# ft231x-breakout.net
KiCad netlist of a schematic drawn in EAGLE
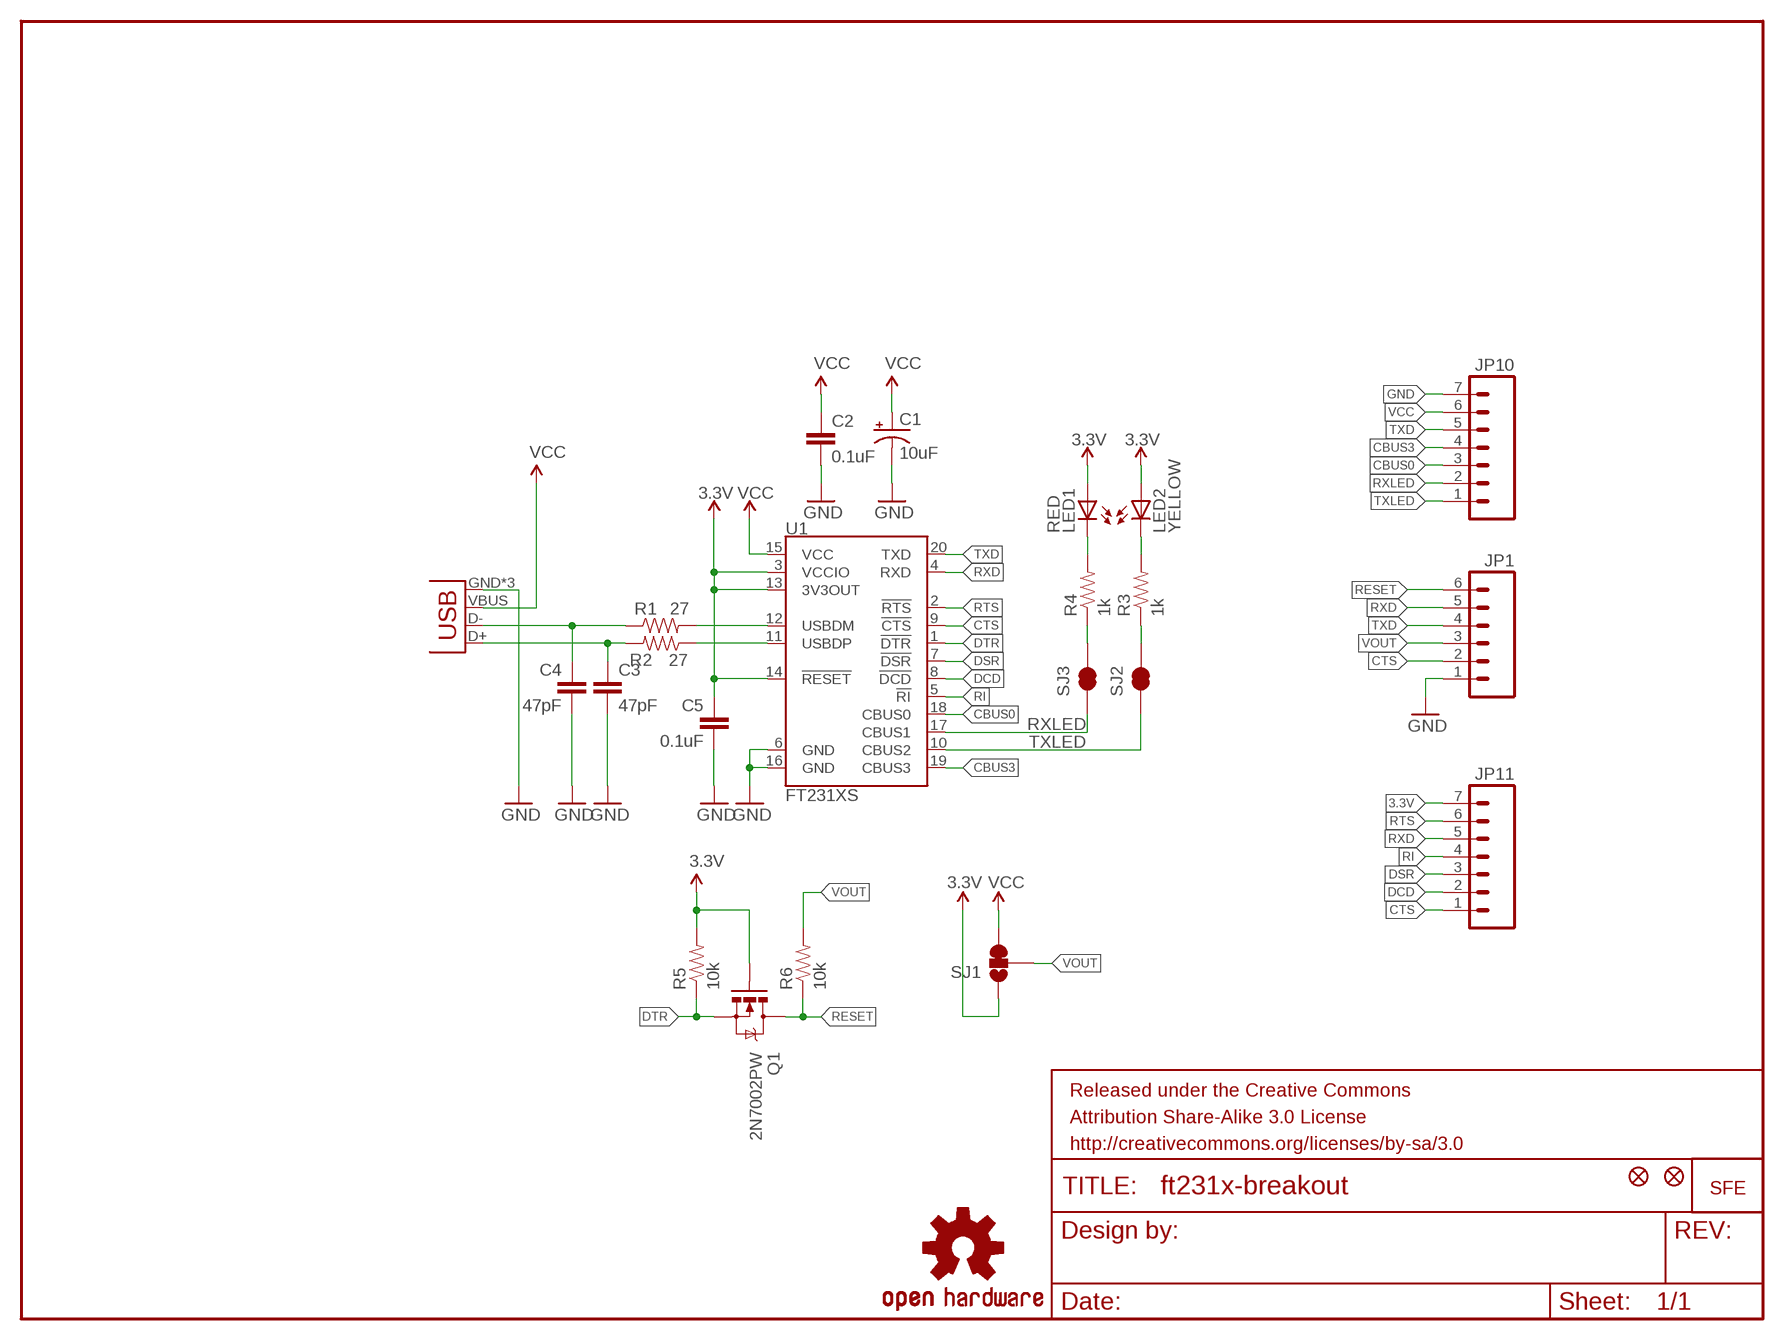
[diagram p0: schematic, sheet 1]

(export (version "E")
  (design (tool "Eeschema 10.0.6"))
  (components
    (comp (ref "C1")
      (value "10uF")
      (footprint "eagle-import:EIA3216")
      (libsource (lib "eagle-import") (part "CAP_POL1206"))
    )
    (comp (ref "C2")
      (value "0.1uF")
      (footprint "eagle-import:0402-CAP")
      (libsource (lib "eagle-import") (part "CAP0402-CAP"))
    )
    (comp (ref "C3")
      (value "47pF")
      (footprint "eagle-import:0402-CAP")
      (libsource (lib "eagle-import") (part "CAP0402-CAP"))
    )
    (comp (ref "C4")
      (value "47pF")
      (footprint "eagle-import:0402-CAP")
      (libsource (lib "eagle-import") (part "CAP0402-CAP"))
    )
    (comp (ref "C5")
      (value "0.1uF")
      (footprint "eagle-import:0402-CAP")
      (libsource (lib "eagle-import") (part "CAP0402-CAP"))
    )
    (comp (ref "FRAME1")
      (value "FRAME-LETTER")
      (footprint "eagle-import:CREATIVE_COMMONS")
      (libsource (lib "eagle-import") (part "FRAME-LETTER"))
    )
    (comp (ref "JP1")
      (value "M06SIP-NS")
      (footprint "eagle-import:1X06_NS")
      (libsource (lib "eagle-import") (part "M06SIP-NS"))
    )
    (comp (ref "JP2")
      (value "LOGO-SFENW2")
      (footprint "eagle-import:SFE-NEW-WEB")
      (libsource (lib "eagle-import") (part "LOGO-SFENW2"))
    )
    (comp (ref "JP3")
      (value "FIDUCIALUFIDUCIAL")
      (footprint "eagle-import:MICRO-FIDUCIAL")
      (libsource (lib "eagle-import") (part "FIDUCIALUFIDUCIAL"))
    )
    (comp (ref "JP4")
      (value "FIDUCIALUFIDUCIAL")
      (footprint "eagle-import:MICRO-FIDUCIAL")
      (libsource (lib "eagle-import") (part "FIDUCIALUFIDUCIAL"))
    )
    (comp (ref "JP10")
      (value "M07NS")
      (footprint "eagle-import:1X07_NS")
      (libsource (lib "eagle-import") (part "M07NS"))
    )
    (comp (ref "JP11")
      (value "M07NS")
      (footprint "eagle-import:1X07_NS")
      (libsource (lib "eagle-import") (part "M07NS"))
    )
    (comp (ref "LED1")
      (value "RED")
      (footprint "eagle-import:LED-0603")
      (libsource (lib "eagle-import") (part "LED0603"))
    )
    (comp (ref "LED2")
      (value "YELLOW")
      (footprint "eagle-import:LED-0603")
      (libsource (lib "eagle-import") (part "LED0603"))
    )
    (comp (ref "Q1")
      (value "2N7002PW")
      (footprint "eagle-import:SOT323")
      (libsource (lib "eagle-import") (part "MOSFET-NCHANNELSOT323"))
    )
    (comp (ref "R1")
      (value "27")
      (footprint "eagle-import:0402-RES")
      (libsource (lib "eagle-import") (part "SparkFun-Resistors_RESISTOR0402-RES"))
    )
    (comp (ref "R2")
      (value "27")
      (footprint "eagle-import:0402-RES")
      (libsource (lib "eagle-import") (part "SparkFun-Resistors_RESISTOR0402-RES"))
    )
    (comp (ref "R3")
      (value "1k")
      (footprint "eagle-import:0402-RES")
      (libsource (lib "eagle-import") (part "RESISTOR0402-RES"))
    )
    (comp (ref "R4")
      (value "1k")
      (footprint "eagle-import:0402-RES")
      (libsource (lib "eagle-import") (part "RESISTOR0402-RES"))
    )
    (comp (ref "R5")
      (value "10k")
      (footprint "eagle-import:0402-RES")
      (libsource (lib "eagle-import") (part "RESISTOR0402-RES"))
    )
    (comp (ref "R6")
      (value "10k")
      (footprint "eagle-import:0402-RES")
      (libsource (lib "eagle-import") (part "RESISTOR0402-RES"))
    )
    (comp (ref "SJ1")
      (value "SOLDERJUMPER_2WAYS")
      (footprint "eagle-import:SJ_3")
      (libsource (lib "eagle-import") (part "SOLDERJUMPER_2WAYS"))
    )
    (comp (ref "SJ2")
      (value "TXLED")
      (footprint "eagle-import:SJ_2S-TRACE")
      (libsource (lib "eagle-import") (part "SOLDERJUMPERTRACE"))
    )
    (comp (ref "SJ3")
      (value "RXLED")
      (footprint "eagle-import:SJ_2S-TRACE")
      (libsource (lib "eagle-import") (part "SOLDERJUMPERTRACE"))
    )
    (comp (ref "U$1")
      (value "OSHW-LOGOS")
      (footprint "eagle-import:OSHW-LOGO-S")
      (libsource (lib "eagle-import") (part "OSHW-LOGOS"))
    )
    (comp (ref "U1")
      (value "FT231XS")
      (footprint "eagle-import:SSOP20_L")
      (libsource (lib "eagle-import") (part "FT231XS"))
    )
    (comp (ref "X1")
      (value "USB-MICROB")
      (footprint "eagle-import:USB-MICROB")
      (libsource (lib "eagle-import") (part "USB-MICROB"))
    )
  )
  (nets
    (net (code "1") (name "3.3V") (class "Default")
      (node (ref "C5") (pin "1") (pinfunction "1_1") (pintype "passive"))
      (node (ref "JP11") (pin "7") (pinfunction "7_7") (pintype "passive"))
      (node (ref "LED1") (pin "A") (pinfunction "A_A") (pintype "passive"))
      (node (ref "LED2") (pin "A") (pinfunction "A_A") (pintype "passive"))
      (node (ref "Q1") (pin "1") (pinfunction "G_1") (pintype "passive"))
      (node (ref "R5") (pin "2") (pinfunction "2_2") (pintype "passive"))
      (node (ref "SJ1") (pin "1") (pinfunction "1_1") (pintype "passive"))
      (node (ref "U1") (pin "13") (pinfunction "3V3OUT_13") (pintype "bidirectional"))
      (node (ref "U1") (pin "14") (pinfunction "~{RESET}_14") (pintype "bidirectional"))
      (node (ref "U1") (pin "3") (pinfunction "VCCIO_3") (pintype "bidirectional"))
    )
    (net (code "2") (name "CBUS0") (class "Default")
      (node (ref "JP10") (pin "3") (pinfunction "3_3") (pintype "passive"))
      (node (ref "U1") (pin "18") (pinfunction "CBUS0_18") (pintype "bidirectional"))
    )
    (net (code "3") (name "CBUS3") (class "Default")
      (node (ref "JP10") (pin "4") (pinfunction "4_4") (pintype "passive"))
      (node (ref "U1") (pin "19") (pinfunction "CBUS3_19") (pintype "bidirectional"))
    )
    (net (code "4") (name "CTS") (class "Default")
      (node (ref "JP1") (pin "2") (pinfunction "2_2") (pintype "passive"))
      (node (ref "JP11") (pin "1") (pinfunction "1_1") (pintype "passive"))
      (node (ref "U1") (pin "9") (pinfunction "~{CTS}_9") (pintype "bidirectional"))
    )
    (net (code "5") (name "DCD") (class "Default")
      (node (ref "JP11") (pin "2") (pinfunction "2_2") (pintype "passive"))
      (node (ref "U1") (pin "8") (pinfunction "~{DCD}_8") (pintype "bidirectional"))
    )
    (net (code "6") (name "DSR") (class "Default")
      (node (ref "JP11") (pin "3") (pinfunction "3_3") (pintype "passive"))
      (node (ref "U1") (pin "7") (pinfunction "~{DSR}_7") (pintype "bidirectional"))
    )
    (net (code "7") (name "DTR") (class "Default")
      (node (ref "Q1") (pin "2") (pinfunction "S_2") (pintype "passive"))
      (node (ref "R5") (pin "1") (pinfunction "1_1") (pintype "passive"))
      (node (ref "U1") (pin "1") (pinfunction "~{DTR}_1") (pintype "bidirectional"))
    )
    (net (code "8") (name "GND") (class "Default")
      (node (ref "C1") (pin "C") (pinfunction "-_C") (pintype "passive"))
      (node (ref "C2") (pin "2") (pinfunction "2_2") (pintype "passive"))
      (node (ref "C3") (pin "2") (pinfunction "2_2") (pintype "passive"))
      (node (ref "C4") (pin "2") (pinfunction "2_2") (pintype "passive"))
      (node (ref "C5") (pin "2") (pinfunction "2_2") (pintype "passive"))
      (node (ref "JP1") (pin "1") (pinfunction "1_1") (pintype "passive"))
      (node (ref "JP10") (pin "7") (pinfunction "7_7") (pintype "passive"))
      (node (ref "U1") (pin "16") (pinfunction "GND_16") (pintype "bidirectional"))
      (node (ref "U1") (pin "6") (pinfunction "GND_6") (pintype "bidirectional"))
      (node (ref "X1") (pin "GND") (pinfunction "GND_GND") (pintype "bidirectional"))
      (node (ref "X1") (pin "MT1") (pinfunction "GND_MT1") (pintype "bidirectional"))
      (node (ref "X1") (pin "MT2") (pinfunction "GND_MT2") (pintype "bidirectional"))
    )
    (net (code "9") (name "Net-(C3-Pad1)") (class "Default")
      (node (ref "C3") (pin "1") (pinfunction "1_1") (pintype "passive"))
      (node (ref "R2") (pin "2") (pinfunction "2_2") (pintype "passive"))
      (node (ref "X1") (pin "D+") (pinfunction "D+_D+") (pintype "bidirectional"))
    )
    (net (code "10") (name "Net-(C4-Pad1)") (class "Default")
      (node (ref "C4") (pin "1") (pinfunction "1_1") (pintype "passive"))
      (node (ref "R1") (pin "1") (pinfunction "1_1") (pintype "passive"))
      (node (ref "X1") (pin "D-") (pinfunction "D-_D-") (pintype "bidirectional"))
    )
    (net (code "11") (name "Net-(LED1-PadC)") (class "Default")
      (node (ref "LED1") (pin "C") (pinfunction "C_C") (pintype "passive"))
      (node (ref "R4") (pin "2") (pinfunction "2_2") (pintype "passive"))
    )
    (net (code "12") (name "Net-(LED2-PadC)") (class "Default")
      (node (ref "LED2") (pin "C") (pinfunction "C_C") (pintype "passive"))
      (node (ref "R3") (pin "2") (pinfunction "2_2") (pintype "passive"))
    )
    (net (code "13") (name "Net-(R3-Pad1)") (class "Default")
      (node (ref "R3") (pin "1") (pinfunction "1_1") (pintype "passive"))
      (node (ref "SJ2") (pin "2") (pinfunction "2_2") (pintype "passive"))
    )
    (net (code "14") (name "Net-(R4-Pad1)") (class "Default")
      (node (ref "R4") (pin "1") (pinfunction "1_1") (pintype "passive"))
      (node (ref "SJ3") (pin "2") (pinfunction "2_2") (pintype "passive"))
    )
    (net (code "15") (name "Net-(U1-USBDM)") (class "Default")
      (node (ref "R1") (pin "2") (pinfunction "2_2") (pintype "passive"))
      (node (ref "U1") (pin "12") (pinfunction "USBDM_12") (pintype "bidirectional"))
    )
    (net (code "16") (name "Net-(U1-USBDP)") (class "Default")
      (node (ref "R2") (pin "1") (pinfunction "1_1") (pintype "passive"))
      (node (ref "U1") (pin "11") (pinfunction "USBDP_11") (pintype "bidirectional"))
    )
    (net (code "17") (name "RESET") (class "Default")
      (node (ref "JP1") (pin "6") (pinfunction "6_6") (pintype "passive"))
      (node (ref "Q1") (pin "3") (pinfunction "D_3") (pintype "passive"))
      (node (ref "R6") (pin "1") (pinfunction "1_1") (pintype "passive"))
    )
    (net (code "18") (name "RI") (class "Default")
      (node (ref "JP11") (pin "4") (pinfunction "4_4") (pintype "passive"))
      (node (ref "U1") (pin "5") (pinfunction "~{RI}_5") (pintype "bidirectional"))
    )
    (net (code "19") (name "RTS") (class "Default")
      (node (ref "JP11") (pin "6") (pinfunction "6_6") (pintype "passive"))
      (node (ref "U1") (pin "2") (pinfunction "~{RTS}_2") (pintype "bidirectional"))
    )
    (net (code "20") (name "RXD") (class "Default")
      (node (ref "JP1") (pin "5") (pinfunction "5_5") (pintype "passive"))
      (node (ref "JP11") (pin "5") (pinfunction "5_5") (pintype "passive"))
      (node (ref "U1") (pin "4") (pinfunction "RXD_4") (pintype "bidirectional"))
    )
    (net (code "21") (name "RXLED") (class "Default")
      (node (ref "JP10") (pin "2") (pinfunction "2_2") (pintype "passive"))
      (node (ref "SJ3") (pin "1") (pinfunction "1_1") (pintype "passive"))
      (node (ref "U1") (pin "17") (pinfunction "CBUS1_17") (pintype "bidirectional"))
    )
    (net (code "22") (name "TXD") (class "Default")
      (node (ref "JP1") (pin "4") (pinfunction "4_4") (pintype "passive"))
      (node (ref "JP10") (pin "5") (pinfunction "5_5") (pintype "passive"))
      (node (ref "U1") (pin "20") (pinfunction "TXD_20") (pintype "bidirectional"))
    )
    (net (code "23") (name "TXLED") (class "Default")
      (node (ref "JP10") (pin "1") (pinfunction "1_1") (pintype "passive"))
      (node (ref "SJ2") (pin "1") (pinfunction "1_1") (pintype "passive"))
      (node (ref "U1") (pin "10") (pinfunction "CBUS2_10") (pintype "bidirectional"))
    )
    (net (code "24") (name "VCC") (class "Default")
      (node (ref "C1") (pin "A") (pinfunction "+_A") (pintype "passive"))
      (node (ref "C2") (pin "1") (pinfunction "1_1") (pintype "passive"))
      (node (ref "JP10") (pin "6") (pinfunction "6_6") (pintype "passive"))
      (node (ref "SJ1") (pin "3") (pinfunction "3_3") (pintype "passive"))
      (node (ref "U1") (pin "15") (pinfunction "VCC_15") (pintype "bidirectional"))
      (node (ref "X1") (pin "VBUS") (pinfunction "VBUS_VBUS") (pintype "bidirectional"))
    )
    (net (code "25") (name "VOUT") (class "Default")
      (node (ref "JP1") (pin "3") (pinfunction "3_3") (pintype "passive"))
      (node (ref "R6") (pin "2") (pinfunction "2_2") (pintype "passive"))
      (node (ref "SJ1") (pin "2") (pinfunction "2_2") (pintype "passive"))
    )
  )
)
